# WYM12864_Adapter_-_MARKS.net
KiCad netlist of a schematic drawn in EAGLE
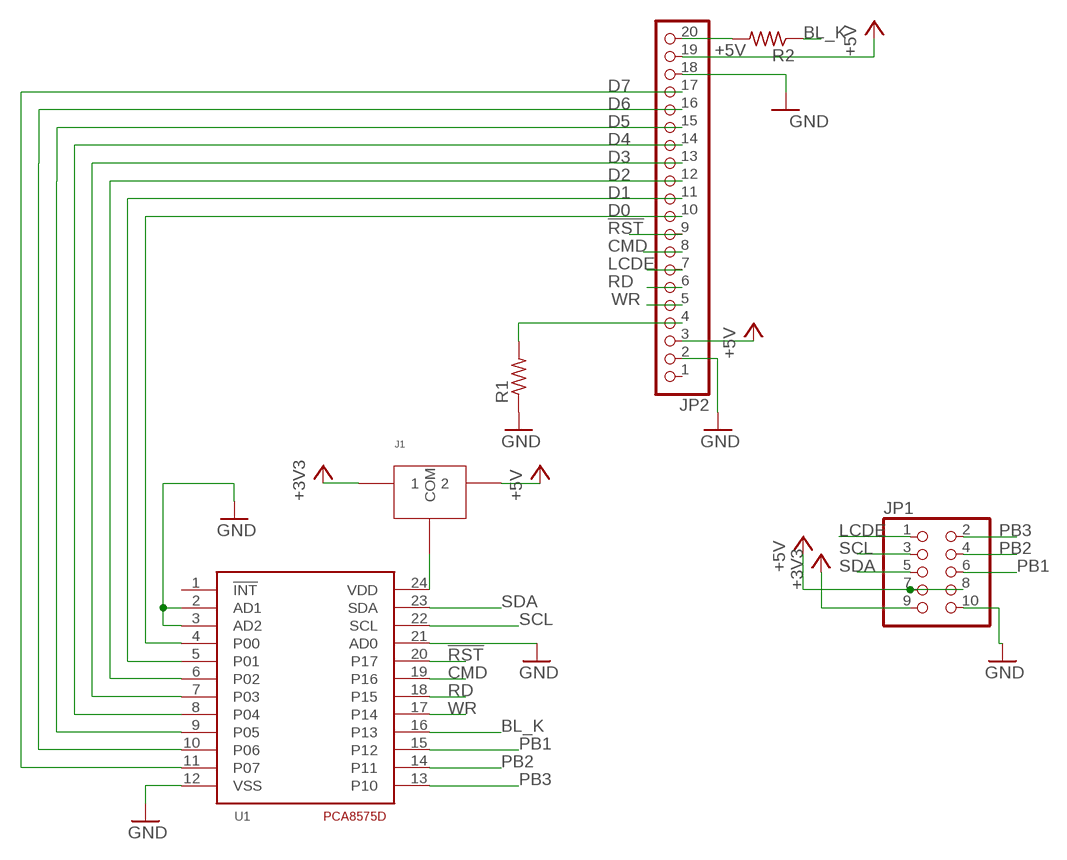
[diagram p0: schematic, sheet 1]

(export (version "E")
  (design (tool "Eeschema 10.0.6"))
  (components
    (comp (ref "J1")
      (value "JMP_3WAY")
      (footprint "eagle-import:JUMPER_THREEWAY")
      (libsource (lib "eagle-import") (part "JMP_3WAY"))
    )
    (comp (ref "JP1")
      (value "PINHD-2X5")
      (footprint "eagle-import:2X05")
      (libsource (lib "eagle-import") (part "PINHD-2X5"))
    )
    (comp (ref "JP2")
      (value "PINHD-1X20")
      (footprint "eagle-import:1X20")
      (libsource (lib "eagle-import") (part "PINHD-1X20"))
    )
    (comp (ref "R1")
      (value "R-US_M0805")
      (footprint "eagle-import:M0805")
      (libsource (lib "eagle-import") (part "R-US_M0805"))
    )
    (comp (ref "R2")
      (value "R-US_M0805")
      (footprint "eagle-import:M0805")
      (libsource (lib "eagle-import") (part "R-US_M0805"))
    )
    (comp (ref "U1")
      (value "PCA8575DSOIC-24")
      (footprint "eagle-import:SOIC-24")
      (libsource (lib "eagle-import") (part "PCA8575DSOIC-24"))
    )
  )
  (nets
    (net (code "1") (name "+3V3") (class "Default")
      (node (ref "J1") (pin "1") (pinfunction "1_1") (pintype "bidirectional"))
      (node (ref "JP1") (pin "9") (pinfunction "9_9") (pintype "passive"))
    )
    (net (code "2") (name "+5V") (class "Default")
      (node (ref "J1") (pin "2") (pinfunction "2_2") (pintype "bidirectional"))
      (node (ref "JP1") (pin "7") (pinfunction "7_7") (pintype "passive"))
      (node (ref "JP1") (pin "8") (pinfunction "8_8") (pintype "passive"))
      (node (ref "JP2") (pin "19") (pinfunction "19_19") (pintype "passive"))
      (node (ref "JP2") (pin "3") (pinfunction "3_3") (pintype "passive"))
    )
    (net (code "3") (name "/BL_K") (class "Default")
      (node (ref "R2") (pin "1") (pinfunction "1_1") (pintype "passive"))
      (node (ref "U1") (pin "16") (pinfunction "P13_16") (pintype "bidirectional"))
    )
    (net (code "4") (name "/CMD") (class "Default")
      (node (ref "JP2") (pin "8") (pinfunction "8_8") (pintype "passive"))
      (node (ref "U1") (pin "19") (pinfunction "P16_19") (pintype "bidirectional"))
    )
    (net (code "5") (name "/D0") (class "Default")
      (node (ref "JP2") (pin "10") (pinfunction "10_10") (pintype "passive"))
      (node (ref "U1") (pin "4") (pinfunction "P00_4") (pintype "bidirectional"))
    )
    (net (code "6") (name "/D1") (class "Default")
      (node (ref "JP2") (pin "11") (pinfunction "11_11") (pintype "passive"))
      (node (ref "U1") (pin "5") (pinfunction "P01_5") (pintype "bidirectional"))
    )
    (net (code "7") (name "/D2") (class "Default")
      (node (ref "JP2") (pin "12") (pinfunction "12_12") (pintype "passive"))
      (node (ref "U1") (pin "6") (pinfunction "P02_6") (pintype "bidirectional"))
    )
    (net (code "8") (name "/D3") (class "Default")
      (node (ref "JP2") (pin "13") (pinfunction "13_13") (pintype "passive"))
      (node (ref "U1") (pin "7") (pinfunction "P03_7") (pintype "bidirectional"))
    )
    (net (code "9") (name "/D4") (class "Default")
      (node (ref "JP2") (pin "14") (pinfunction "14_14") (pintype "passive"))
      (node (ref "U1") (pin "8") (pinfunction "P04_8") (pintype "bidirectional"))
    )
    (net (code "10") (name "/D5") (class "Default")
      (node (ref "JP2") (pin "15") (pinfunction "15_15") (pintype "passive"))
      (node (ref "U1") (pin "9") (pinfunction "P05_9") (pintype "bidirectional"))
    )
    (net (code "11") (name "/D6") (class "Default")
      (node (ref "JP2") (pin "16") (pinfunction "16_16") (pintype "passive"))
      (node (ref "U1") (pin "10") (pinfunction "P06_10") (pintype "bidirectional"))
    )
    (net (code "12") (name "/D7") (class "Default")
      (node (ref "JP2") (pin "17") (pinfunction "17_17") (pintype "passive"))
      (node (ref "U1") (pin "11") (pinfunction "P07_11") (pintype "bidirectional"))
    )
    (net (code "13") (name "/LCDE") (class "Default")
      (node (ref "JP1") (pin "1") (pinfunction "1_1") (pintype "passive"))
      (node (ref "JP2") (pin "7") (pinfunction "7_7") (pintype "passive"))
    )
    (net (code "14") (name "/PB1") (class "Default")
      (node (ref "JP1") (pin "6") (pinfunction "6_6") (pintype "passive"))
      (node (ref "U1") (pin "15") (pinfunction "P12_15") (pintype "bidirectional"))
    )
    (net (code "15") (name "/PB2") (class "Default")
      (node (ref "JP1") (pin "4") (pinfunction "4_4") (pintype "passive"))
      (node (ref "U1") (pin "14") (pinfunction "P11_14") (pintype "bidirectional"))
    )
    (net (code "16") (name "/PB3") (class "Default")
      (node (ref "JP1") (pin "2") (pinfunction "2_2") (pintype "passive"))
      (node (ref "U1") (pin "13") (pinfunction "P10_13") (pintype "bidirectional"))
    )
    (net (code "17") (name "/RD") (class "Default")
      (node (ref "JP2") (pin "6") (pinfunction "6_6") (pintype "passive"))
      (node (ref "U1") (pin "18") (pinfunction "P15_18") (pintype "bidirectional"))
    )
    (net (code "18") (name "/SCL") (class "Default")
      (node (ref "JP1") (pin "3") (pinfunction "3_3") (pintype "passive"))
      (node (ref "U1") (pin "22") (pinfunction "SCL_22") (pintype "bidirectional"))
    )
    (net (code "19") (name "/SDA") (class "Default")
      (node (ref "JP1") (pin "5") (pinfunction "5_5") (pintype "passive"))
      (node (ref "U1") (pin "23") (pinfunction "SDA_23") (pintype "bidirectional"))
    )
    (net (code "20") (name "/WR") (class "Default")
      (node (ref "JP2") (pin "5") (pinfunction "5_5") (pintype "passive"))
      (node (ref "U1") (pin "17") (pinfunction "P14_17") (pintype "bidirectional"))
    )
    (net (code "21") (name "/~{RST}") (class "Default")
      (node (ref "JP2") (pin "9") (pinfunction "9_9") (pintype "passive"))
      (node (ref "U1") (pin "20") (pinfunction "P17_20") (pintype "bidirectional"))
    )
    (net (code "22") (name "GND") (class "Default")
      (node (ref "JP1") (pin "10") (pinfunction "10_10") (pintype "passive"))
      (node (ref "JP2") (pin "18") (pinfunction "18_18") (pintype "passive"))
      (node (ref "JP2") (pin "2") (pinfunction "2_2") (pintype "passive"))
      (node (ref "R1") (pin "1") (pinfunction "1_1") (pintype "passive"))
      (node (ref "U1") (pin "12") (pinfunction "VSS_12") (pintype "bidirectional"))
      (node (ref "U1") (pin "2") (pinfunction "AD1_2") (pintype "bidirectional"))
      (node (ref "U1") (pin "21") (pinfunction "AD0_21") (pintype "bidirectional"))
      (node (ref "U1") (pin "3") (pinfunction "AD2_3") (pintype "bidirectional"))
    )
    (net (code "23") (name "Net-(J1-COM)") (class "Default")
      (node (ref "J1") (pin "C") (pinfunction "COM_C") (pintype "bidirectional"))
      (node (ref "U1") (pin "24") (pinfunction "VDD_24") (pintype "bidirectional"))
    )
    (net (code "24") (name "Net-(JP2-Pad4)") (class "Default")
      (node (ref "JP2") (pin "4") (pinfunction "4_4") (pintype "passive"))
      (node (ref "R1") (pin "2") (pinfunction "2_2") (pintype "passive"))
    )
    (net (code "25") (name "Net-(JP2-Pad20)") (class "Default")
      (node (ref "JP2") (pin "20") (pinfunction "20_20") (pintype "passive"))
      (node (ref "R2") (pin "2") (pinfunction "2_2") (pintype "passive"))
    )
    (net (code "26") (name "unconnected-(JP2-Pad1)") (class "Default")
      (node (ref "JP2") (pin "1") (pinfunction "1_1") (pintype "passive"))
    )
    (net (code "27") (name "unconnected-(U1-~{INT}-Pad1)") (class "Default")
      (node (ref "U1") (pin "1") (pinfunction "~{INT}_1") (pintype "bidirectional"))
    )
  )
)
